# Driver_Morpheus_v5_2_SENSOR_CORRENTE.net
KiCad netlist of a schematic drawn in Altium Designer
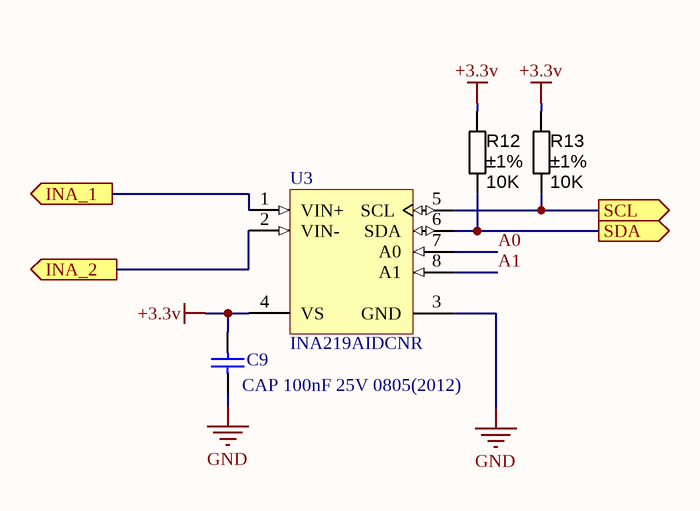
[diagram p0: Driver Morpheus v5.2 SENSOR CORRENTE.SchDoc]

(export (version "E")
  (design (tool "Eeschema 10.0.6"))
  (components
    (comp (ref "C9")
      (value "CAP 100nF 25V 0805(2012)")
      (footprint "CAPC0805(2012)145_M")
      (description "CAP 100nF 25V ±5% 0805 (2012 Metric) Thickness 1.45mm SMD")
      (fields (field (name "TOLERANCE") "Â±5%"))
      (libsource (lib "Altium Content Vault") (part "CAP"))
    )
    (comp (ref "R12")
      (value "10K")
      (footprint "RESC1608X55N")
      (description "Resistor SMD chip 10k Ohm 0.1W 1% 0603")
      (fields (field (name "TOLERANCE") "±1%") (field (name "Comment") "Thick Film"))
      (libsource (lib "PBL - Resistors") (part "RES_10K_0603_1%"))
    )
    (comp (ref "R13")
      (value "10K")
      (footprint "RESC1608X55N")
      (description "Resistor SMD chip 10k Ohm 0.1W 1% 0603")
      (fields (field (name "TOLERANCE") "±1%") (field (name "Comment") "Thick Film"))
      (libsource (lib "PBL - Resistors") (part "RES_10K_0603_1%"))
    )
    (comp (ref "U3")
      (value "INA219AIDCNR")
      (footprint "DCN0008A_M")
      (fields (field (name "MANUFACTURER") "Texas Instruments"))
      (libsource (lib "Altium Content Vault") (part "TI-INA219DCN8"))
    )
  )
  (nets
    (net (code "1") (name "+3.3v") (class "Default")
      (node (ref "C9") (pin "2") (pinfunction "2_2") (pintype "passive"))
      (node (ref "R12") (pin "1") (pinfunction "1_1") (pintype "passive"))
      (node (ref "R13") (pin "1") (pinfunction "1_1") (pintype "passive"))
      (node (ref "U3") (pin "4") (pinfunction "VS_4") (pintype "power_in"))
    )
    (net (code "2") (name "/A0") (class "Default")
      (node (ref "U3") (pin "7") (pinfunction "A0_7") (pintype "input"))
    )
    (net (code "3") (name "/A1") (class "Default")
      (node (ref "U3") (pin "8") (pinfunction "A1_8") (pintype "input"))
    )
    (net (code "4") (name "/INA_1") (class "Default")
      (node (ref "U3") (pin "1") (pinfunction "VIN+_1") (pintype "input"))
    )
    (net (code "5") (name "/INA_2") (class "Default")
      (node (ref "U3") (pin "2") (pinfunction "VIN-_2") (pintype "input"))
    )
    (net (code "6") (name "/SCL") (class "Default")
      (node (ref "R13") (pin "2") (pinfunction "2_2") (pintype "passive"))
      (node (ref "U3") (pin "5") (pinfunction "SCL_5") (pintype "bidirectional"))
    )
    (net (code "7") (name "/SDA") (class "Default")
      (node (ref "R12") (pin "2") (pinfunction "2_2") (pintype "passive"))
      (node (ref "U3") (pin "6") (pinfunction "SDA_6") (pintype "bidirectional"))
    )
    (net (code "8") (name "GND") (class "Default")
      (node (ref "C9") (pin "1") (pinfunction "1_1") (pintype "passive"))
      (node (ref "U3") (pin "3") (pinfunction "GND_3") (pintype "power_in"))
    )
  )
)
